# G009B.net
KiCad netlist of a schematic drawn in EAGLE
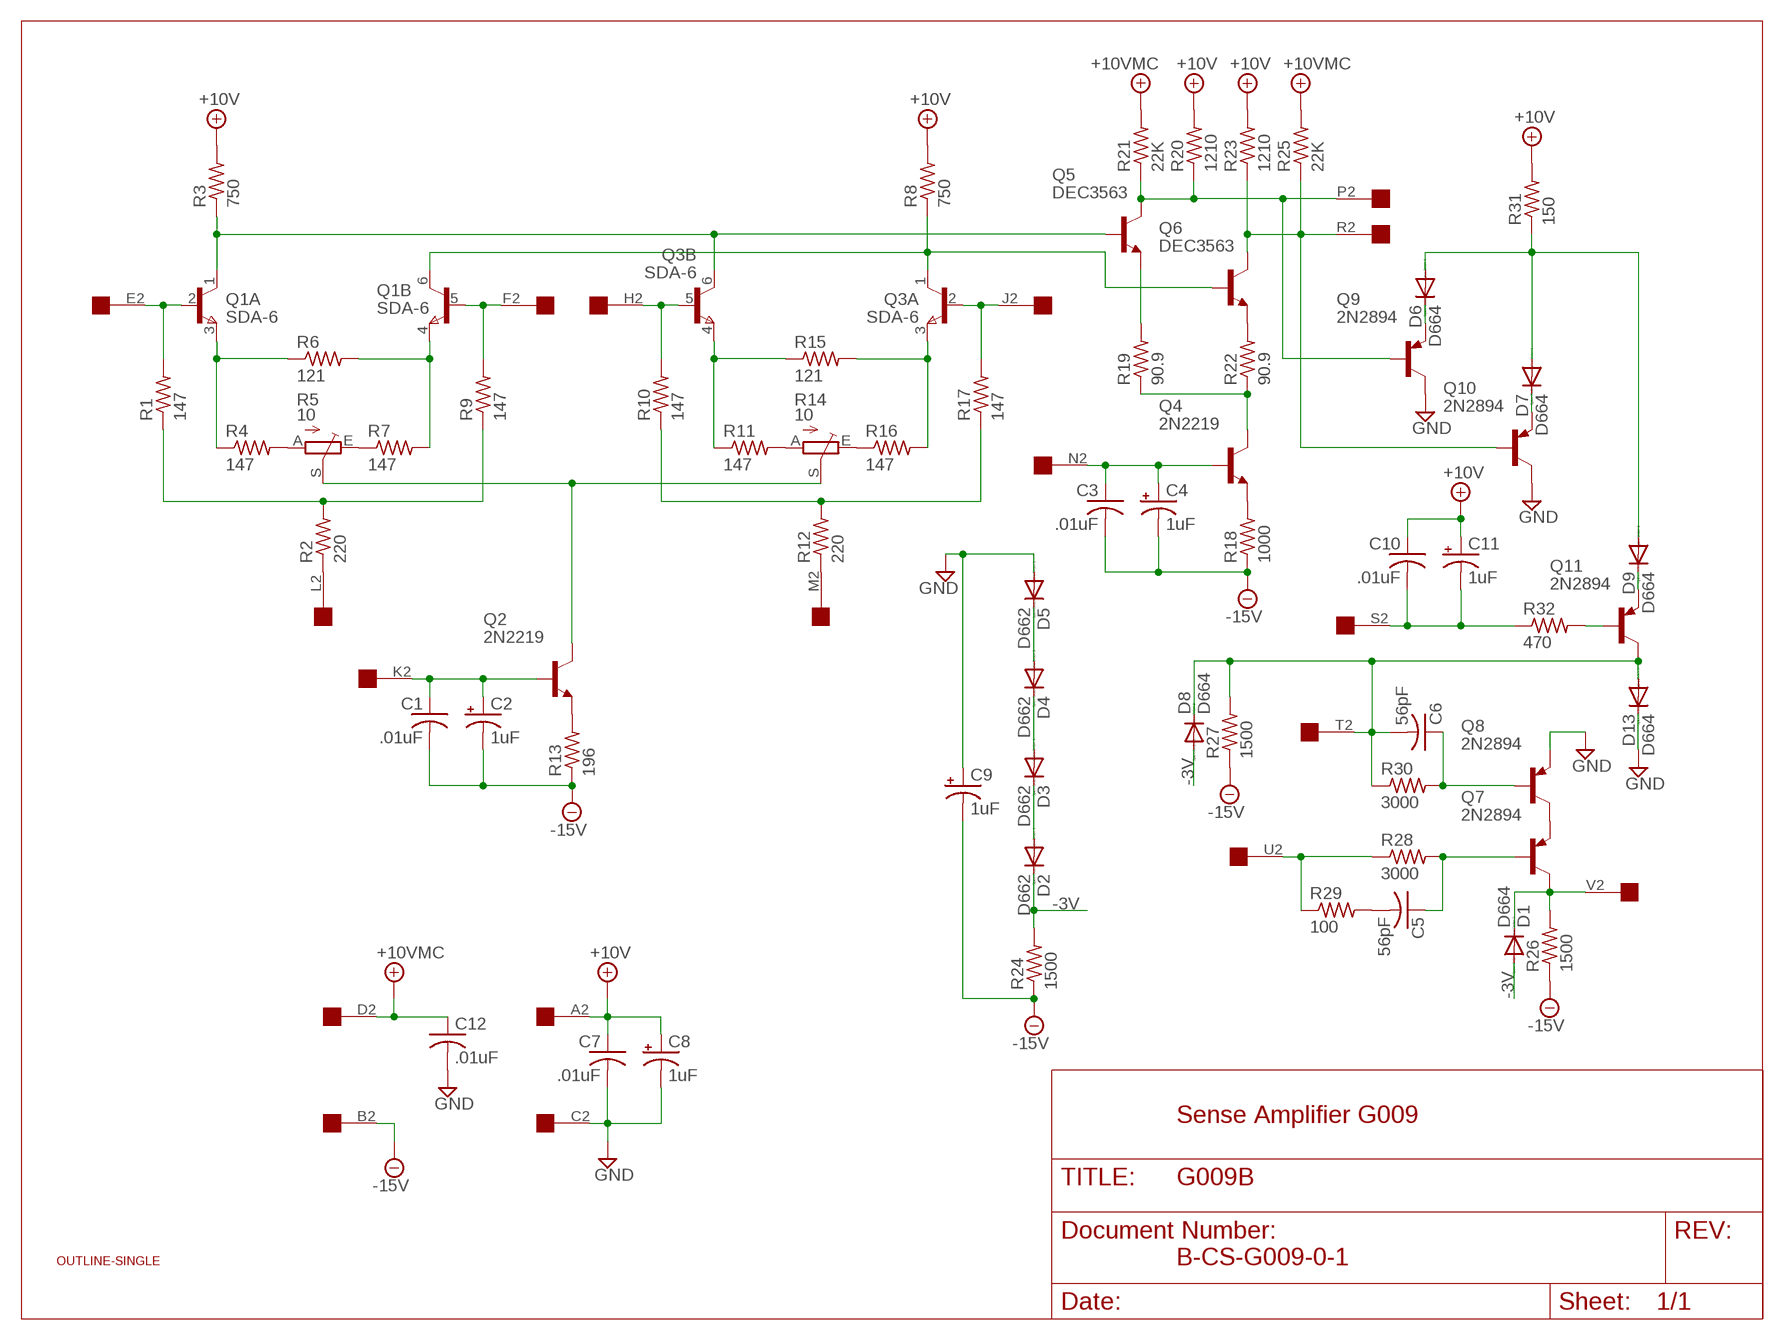
[diagram p0: schematic, sheet 1]

(export (version "E")
  (design (tool "Eeschema 10.0.6"))
  (components
    (comp (ref "C1")
      (value ".01uF")
      (footprint "eagle-import:C063-025X075")
      (libsource (lib "eagle-import") (part "C-US"))
    )
    (comp (ref "C2")
      (value "1uF")
      (footprint "eagle-import:E15-5")
      (libsource (lib "eagle-import") (part "CPOL-USE15-5AXIAL"))
    )
    (comp (ref "C3")
      (value ".01uF")
      (footprint "eagle-import:C063-025X075")
      (libsource (lib "eagle-import") (part "C-US"))
    )
    (comp (ref "C4")
      (value "1uF")
      (footprint "eagle-import:E15-5")
      (libsource (lib "eagle-import") (part "CPOL-USE15-5AXIAL"))
    )
    (comp (ref "C5")
      (value "56pF")
      (footprint "eagle-import:C150-054X183")
      (libsource (lib "eagle-import") (part "C-US150-054X183"))
    )
    (comp (ref "C6")
      (value "56pF")
      (footprint "eagle-import:C150-054X183")
      (libsource (lib "eagle-import") (part "C-US150-054X183"))
    )
    (comp (ref "C7")
      (value ".01uF")
      (footprint "eagle-import:C063-025X075")
      (libsource (lib "eagle-import") (part "C-US"))
    )
    (comp (ref "C8")
      (value "1uF")
      (footprint "eagle-import:E15-5")
      (libsource (lib "eagle-import") (part "CPOL-USE15-5AXIAL"))
    )
    (comp (ref "C9")
      (value "1uF")
      (footprint "eagle-import:E15-5")
      (libsource (lib "eagle-import") (part "CPOL-USE15-5AXIAL"))
    )
    (comp (ref "C10")
      (value ".01uF")
      (footprint "eagle-import:C063-025X075")
      (libsource (lib "eagle-import") (part "C-US"))
    )
    (comp (ref "C11")
      (value "1uF")
      (footprint "eagle-import:E15-5")
      (libsource (lib "eagle-import") (part "CPOL-USE15-5AXIAL"))
    )
    (comp (ref "C12")
      (value ".01uF")
      (footprint "eagle-import:C063-025X075")
      (libsource (lib "eagle-import") (part "C-US"))
    )
    (comp (ref "D1")
      (value "D664")
      (footprint "eagle-import:DO35-10")
      (libsource (lib "eagle-import") (part "DIODE-DO35-10"))
    )
    (comp (ref "D2")
      (value "D662")
      (footprint "eagle-import:DO35-10")
      (libsource (lib "eagle-import") (part "DIODE-DO35-10"))
    )
    (comp (ref "D3")
      (value "D662")
      (footprint "eagle-import:DO35-10")
      (libsource (lib "eagle-import") (part "DIODE-DO35-10"))
    )
    (comp (ref "D4")
      (value "D662")
      (footprint "eagle-import:DO35-10")
      (libsource (lib "eagle-import") (part "DIODE-DO35-10"))
    )
    (comp (ref "D5")
      (value "D662")
      (footprint "eagle-import:DO35-10")
      (libsource (lib "eagle-import") (part "DIODE-DO35-10"))
    )
    (comp (ref "D6")
      (value "D664")
      (footprint "eagle-import:DO35-10")
      (libsource (lib "eagle-import") (part "DIODE-DO35-10"))
    )
    (comp (ref "D7")
      (value "D664")
      (footprint "eagle-import:DO35-10")
      (libsource (lib "eagle-import") (part "DIODE-DO35-10"))
    )
    (comp (ref "D8")
      (value "D664")
      (footprint "eagle-import:DO35-10")
      (libsource (lib "eagle-import") (part "DIODE-DO35-10"))
    )
    (comp (ref "D9")
      (value "D664")
      (footprint "eagle-import:DO35-10")
      (libsource (lib "eagle-import") (part "DIODE-DO35-10"))
    )
    (comp (ref "D13")
      (value "D664")
      (footprint "eagle-import:DO35-10")
      (libsource (lib "eagle-import") (part "DIODE-DO35-10"))
    )
    (comp (ref "Q1")
      (value "SDA-6")
      (footprint "eagle-import:TO78")
      (libsource (lib "eagle-import") (part "MAT-01H"))
    )
    (comp (ref "Q2")
      (value "2N2219")
      (footprint "eagle-import:TO5")
      (libsource (lib "eagle-import") (part "2N2219"))
    )
    (comp (ref "Q3")
      (value "SDA-6")
      (footprint "eagle-import:TO78")
      (libsource (lib "eagle-import") (part "MAT-01H"))
    )
    (comp (ref "Q4")
      (value "2N2219")
      (footprint "eagle-import:TO5")
      (libsource (lib "eagle-import") (part "2N2219"))
    )
    (comp (ref "Q5")
      (value "DEC3563")
      (footprint "eagle-import:TO5")
      (libsource (lib "eagle-import") (part "-NPN-TO5"))
    )
    (comp (ref "Q6")
      (value "DEC3563")
      (footprint "eagle-import:TO5")
      (libsource (lib "eagle-import") (part "-NPN-TO5"))
    )
    (comp (ref "Q7")
      (value "2N2894")
      (footprint "eagle-import:TO5")
      (libsource (lib "eagle-import") (part "-PNP-TO5"))
    )
    (comp (ref "Q8")
      (value "2N2894")
      (footprint "eagle-import:TO5")
      (libsource (lib "eagle-import") (part "-PNP-TO5"))
    )
    (comp (ref "Q9")
      (value "2N2894")
      (footprint "eagle-import:TO5")
      (libsource (lib "eagle-import") (part "-PNP-TO5"))
    )
    (comp (ref "Q10")
      (value "2N2894")
      (footprint "eagle-import:TO5")
      (libsource (lib "eagle-import") (part "-PNP-TO5"))
    )
    (comp (ref "Q11")
      (value "2N2894")
      (footprint "eagle-import:TO5")
      (libsource (lib "eagle-import") (part "-PNP-TO5"))
    )
    (comp (ref "R1")
      (value "147")
      (footprint "eagle-import:0207_15")
      (libsource (lib "eagle-import") (part "R-US_0207/15"))
    )
    (comp (ref "R2")
      (value "220")
      (footprint "eagle-import:0207_10")
      (libsource (lib "eagle-import") (part "R-US_0207/10"))
    )
    (comp (ref "R3")
      (value "750")
      (footprint "eagle-import:0207_15")
      (libsource (lib "eagle-import") (part "R-US_0207/15"))
    )
    (comp (ref "R4")
      (value "147")
      (footprint "eagle-import:0207_15")
      (libsource (lib "eagle-import") (part "R-US_0207/15"))
    )
    (comp (ref "R5")
      (value "10")
      (footprint "eagle-import:CT6")
      (libsource (lib "eagle-import") (part "TRIM_EU-CT6"))
    )
    (comp (ref "R6")
      (value "121")
      (footprint "eagle-import:0207_15")
      (libsource (lib "eagle-import") (part "R-US_0207/15"))
    )
    (comp (ref "R7")
      (value "147")
      (footprint "eagle-import:0207_15")
      (libsource (lib "eagle-import") (part "R-US_0207/15"))
    )
    (comp (ref "R8")
      (value "750")
      (footprint "eagle-import:0207_15")
      (libsource (lib "eagle-import") (part "R-US_0207/15"))
    )
    (comp (ref "R9")
      (value "147")
      (footprint "eagle-import:0207_15")
      (libsource (lib "eagle-import") (part "R-US_0207/15"))
    )
    (comp (ref "R10")
      (value "147")
      (footprint "eagle-import:0207_15")
      (libsource (lib "eagle-import") (part "R-US_0207/15"))
    )
    (comp (ref "R11")
      (value "147")
      (footprint "eagle-import:0207_15")
      (libsource (lib "eagle-import") (part "R-US_0207/15"))
    )
    (comp (ref "R12")
      (value "220")
      (footprint "eagle-import:0207_10")
      (libsource (lib "eagle-import") (part "R-US_0207/10"))
    )
    (comp (ref "R13")
      (value "196")
      (footprint "eagle-import:0207_15")
      (libsource (lib "eagle-import") (part "R-US_0207/15"))
    )
    (comp (ref "R14")
      (value "10")
      (footprint "eagle-import:CT6")
      (libsource (lib "eagle-import") (part "TRIM_EU-CT6"))
    )
    (comp (ref "R15")
      (value "121")
      (footprint "eagle-import:0207_15")
      (libsource (lib "eagle-import") (part "R-US_0207/15"))
    )
    (comp (ref "R16")
      (value "147")
      (footprint "eagle-import:0207_15")
      (libsource (lib "eagle-import") (part "R-US_0207/15"))
    )
    (comp (ref "R17")
      (value "147")
      (footprint "eagle-import:0207_15")
      (libsource (lib "eagle-import") (part "R-US_0207/15"))
    )
    (comp (ref "R18")
      (value "1000")
      (footprint "eagle-import:0207_15")
      (libsource (lib "eagle-import") (part "R-US_0207/15"))
    )
    (comp (ref "R19")
      (value "90.9")
      (footprint "eagle-import:0207_15")
      (libsource (lib "eagle-import") (part "R-US_0207/15"))
    )
    (comp (ref "R20")
      (value "1210")
      (footprint "eagle-import:0207_15")
      (libsource (lib "eagle-import") (part "R-US_0207/15"))
    )
    (comp (ref "R21")
      (value "22K")
      (footprint "eagle-import:0207_10")
      (libsource (lib "eagle-import") (part "R-US_0207/10"))
    )
    (comp (ref "R22")
      (value "90.9")
      (footprint "eagle-import:0207_15")
      (libsource (lib "eagle-import") (part "R-US_0207/15"))
    )
    (comp (ref "R23")
      (value "1210")
      (footprint "eagle-import:0207_15")
      (libsource (lib "eagle-import") (part "R-US_0207/15"))
    )
    (comp (ref "R24")
      (value "1500")
      (footprint "eagle-import:0207_10")
      (libsource (lib "eagle-import") (part "R-US_0207/10"))
    )
    (comp (ref "R25")
      (value "22K")
      (footprint "eagle-import:0207_10")
      (libsource (lib "eagle-import") (part "R-US_0207/10"))
    )
    (comp (ref "R26")
      (value "1500")
      (footprint "eagle-import:0207_10")
      (libsource (lib "eagle-import") (part "R-US_0207/10"))
    )
    (comp (ref "R27")
      (value "1500")
      (footprint "eagle-import:0207_10")
      (libsource (lib "eagle-import") (part "R-US_0207/10"))
    )
    (comp (ref "R28")
      (value "3000")
      (footprint "eagle-import:0207_10")
      (libsource (lib "eagle-import") (part "R-US_0207/10"))
    )
    (comp (ref "R29")
      (value "100")
      (footprint "eagle-import:0207_10")
      (libsource (lib "eagle-import") (part "R-US_0207/10"))
    )
    (comp (ref "R30")
      (value "3000")
      (footprint "eagle-import:0207_10")
      (libsource (lib "eagle-import") (part "R-US_0207/10"))
    )
    (comp (ref "R31")
      (value "150")
      (footprint "eagle-import:0207_10")
      (libsource (lib "eagle-import") (part "R-US_0207/10"))
    )
    (comp (ref "R32")
      (value "470")
      (footprint "eagle-import:0207_10")
      (libsource (lib "eagle-import") (part "R-US_0207/10"))
    )
    (comp (ref "U$1")
      (value "OUTLINE-SINGLE")
      (footprint "eagle-import:SINGLE")
      (libsource (lib "eagle-import") (part "OUTLINE-SINGLE"))
    )
    (comp (ref "U$2")
      (value "EDGE-1")
      (footprint "eagle-import:EDGE-CON1")
      (libsource (lib "eagle-import") (part "EDGE-1"))
    )
  )
  (nets
    (net (code "1") (name "+10V") (class "Default")
      (node (ref "C10") (pin "1") (pinfunction "1_1") (pintype "passive"))
      (node (ref "C11") (pin "+") (pinfunction "+_+") (pintype "passive"))
      (node (ref "C7") (pin "1") (pinfunction "1_1") (pintype "passive"))
      (node (ref "C8") (pin "+") (pinfunction "+_+") (pintype "passive"))
      (node (ref "R20") (pin "2") (pinfunction "2_2") (pintype "passive"))
      (node (ref "R23") (pin "2") (pinfunction "2_2") (pintype "passive"))
      (node (ref "R3") (pin "2") (pinfunction "2_2") (pintype "passive"))
      (node (ref "R31") (pin "2") (pinfunction "2_2") (pintype "passive"))
      (node (ref "R8") (pin "2") (pinfunction "2_2") (pintype "passive"))
      (node (ref "U$2") (pin "A2") (pinfunction "1_A2") (pintype "bidirectional"))
    )
    (net (code "2") (name "+10VMC") (class "Default")
      (node (ref "C12") (pin "1") (pinfunction "1_1") (pintype "passive"))
      (node (ref "R21") (pin "2") (pinfunction "2_2") (pintype "passive"))
      (node (ref "R25") (pin "2") (pinfunction "2_2") (pintype "passive"))
      (node (ref "U$2") (pin "D2") (pinfunction "1_D2") (pintype "bidirectional"))
    )
    (net (code "3") (name "-15V") (class "Default")
      (node (ref "C1") (pin "2") (pinfunction "2_2") (pintype "passive"))
      (node (ref "C2") (pin "-") (pinfunction "-_-") (pintype "passive"))
      (node (ref "C3") (pin "2") (pinfunction "2_2") (pintype "passive"))
      (node (ref "C4") (pin "-") (pinfunction "-_-") (pintype "passive"))
      (node (ref "C9") (pin "-") (pinfunction "-_-") (pintype "passive"))
      (node (ref "R13") (pin "1") (pinfunction "1_1") (pintype "passive"))
      (node (ref "R18") (pin "1") (pinfunction "1_1") (pintype "passive"))
      (node (ref "R24") (pin "1") (pinfunction "1_1") (pintype "passive"))
      (node (ref "R26") (pin "1") (pinfunction "1_1") (pintype "passive"))
      (node (ref "R27") (pin "1") (pinfunction "1_1") (pintype "passive"))
      (node (ref "U$2") (pin "B2") (pinfunction "1_B2") (pintype "bidirectional"))
    )
    (net (code "4") (name "/-3V") (class "Default")
      (node (ref "D1") (pin "A") (pinfunction "A_A") (pintype "passive"))
      (node (ref "D2") (pin "C") (pinfunction "C_C") (pintype "passive"))
      (node (ref "D8") (pin "A") (pinfunction "A_A") (pintype "passive"))
      (node (ref "R24") (pin "2") (pinfunction "2_2") (pintype "passive"))
    )
    (net (code "5") (name "GND") (class "Default")
      (node (ref "C12") (pin "2") (pinfunction "2_2") (pintype "passive"))
      (node (ref "C7") (pin "2") (pinfunction "2_2") (pintype "passive"))
      (node (ref "C8") (pin "-") (pinfunction "-_-") (pintype "passive"))
      (node (ref "C9") (pin "+") (pinfunction "+_+") (pintype "passive"))
      (node (ref "D13") (pin "C") (pinfunction "C_C") (pintype "passive"))
      (node (ref "D5") (pin "A") (pinfunction "A_A") (pintype "passive"))
      (node (ref "Q10") (pin "3") (pinfunction "C_3") (pintype "passive"))
      (node (ref "Q8") (pin "1") (pinfunction "E_1") (pintype "passive"))
      (node (ref "Q9") (pin "3") (pinfunction "C_3") (pintype "passive"))
      (node (ref "U$2") (pin "C2") (pinfunction "1_C2") (pintype "bidirectional"))
    )
    (net (code "6") (name "Net-(C5-Pad2)") (class "Default")
      (node (ref "C5") (pin "2") (pinfunction "2_2") (pintype "passive"))
      (node (ref "R29") (pin "2") (pinfunction "2_2") (pintype "passive"))
    )
    (net (code "7") (name "Net-(D2-PadA)") (class "Default")
      (node (ref "D2") (pin "A") (pinfunction "A_A") (pintype "passive"))
      (node (ref "D3") (pin "C") (pinfunction "C_C") (pintype "passive"))
    )
    (net (code "8") (name "Net-(D3-PadA)") (class "Default")
      (node (ref "D3") (pin "A") (pinfunction "A_A") (pintype "passive"))
      (node (ref "D4") (pin "C") (pinfunction "C_C") (pintype "passive"))
    )
    (net (code "9") (name "Net-(D4-PadA)") (class "Default")
      (node (ref "D4") (pin "A") (pinfunction "A_A") (pintype "passive"))
      (node (ref "D5") (pin "C") (pinfunction "C_C") (pintype "passive"))
    )
    (net (code "10") (name "Net-(D6-PadA)") (class "Default")
      (node (ref "D6") (pin "A") (pinfunction "A_A") (pintype "passive"))
      (node (ref "D7") (pin "A") (pinfunction "A_A") (pintype "passive"))
      (node (ref "D9") (pin "A") (pinfunction "A_A") (pintype "passive"))
      (node (ref "R31") (pin "1") (pinfunction "1_1") (pintype "passive"))
    )
    (net (code "11") (name "Net-(Q1A-B)") (class "Default")
      (node (ref "Q1") (pin "2") (pinfunction "B_2") (pintype "passive"))
      (node (ref "R1") (pin "2") (pinfunction "2_2") (pintype "passive"))
      (node (ref "U$2") (pin "E2") (pinfunction "1_E2") (pintype "bidirectional"))
    )
    (net (code "12") (name "Net-(Q1A-C)") (class "Default")
      (node (ref "Q1") (pin "1") (pinfunction "C_1") (pintype "passive"))
      (node (ref "Q3") (pin "6") (pinfunction "C_6") (pintype "passive"))
      (node (ref "Q5") (pin "2") (pinfunction "B_2") (pintype "passive"))
      (node (ref "R3") (pin "1") (pinfunction "1_1") (pintype "passive"))
    )
    (net (code "13") (name "Net-(Q1A-E)") (class "Default")
      (node (ref "Q1") (pin "3") (pinfunction "E_3") (pintype "passive"))
      (node (ref "R4") (pin "1") (pinfunction "1_1") (pintype "passive"))
      (node (ref "R6") (pin "1") (pinfunction "1_1") (pintype "passive"))
    )
    (net (code "14") (name "Net-(Q1B-B)") (class "Default")
      (node (ref "Q1") (pin "5") (pinfunction "B_5") (pintype "passive"))
      (node (ref "R9") (pin "2") (pinfunction "2_2") (pintype "passive"))
      (node (ref "U$2") (pin "F2") (pinfunction "1_F2") (pintype "bidirectional"))
    )
    (net (code "15") (name "Net-(Q1B-C)") (class "Default")
      (node (ref "Q1") (pin "6") (pinfunction "C_6") (pintype "passive"))
      (node (ref "Q3") (pin "1") (pinfunction "C_1") (pintype "passive"))
      (node (ref "Q6") (pin "2") (pinfunction "B_2") (pintype "passive"))
      (node (ref "R8") (pin "1") (pinfunction "1_1") (pintype "passive"))
    )
    (net (code "16") (name "Net-(Q1B-E)") (class "Default")
      (node (ref "Q1") (pin "4") (pinfunction "E_4") (pintype "passive"))
      (node (ref "R6") (pin "2") (pinfunction "2_2") (pintype "passive"))
      (node (ref "R7") (pin "2") (pinfunction "2_2") (pintype "passive"))
    )
    (net (code "17") (name "Net-(Q2-B)") (class "Default")
      (node (ref "C1") (pin "1") (pinfunction "1_1") (pintype "passive"))
      (node (ref "C2") (pin "+") (pinfunction "+_+") (pintype "passive"))
      (node (ref "Q2") (pin "2") (pinfunction "B_2") (pintype "passive"))
      (node (ref "U$2") (pin "K2") (pinfunction "1_K2") (pintype "bidirectional"))
    )
    (net (code "18") (name "Net-(Q2-C)") (class "Default")
      (node (ref "Q2") (pin "3") (pinfunction "C_3") (pintype "passive"))
      (node (ref "R14") (pin "S") (pinfunction "S_S") (pintype "passive"))
      (node (ref "R5") (pin "S") (pinfunction "S_S") (pintype "passive"))
    )
    (net (code "19") (name "Net-(Q2-E)") (class "Default")
      (node (ref "Q2") (pin "1") (pinfunction "E_1") (pintype "passive"))
      (node (ref "R13") (pin "2") (pinfunction "2_2") (pintype "passive"))
    )
    (net (code "20") (name "Net-(Q3A-B)") (class "Default")
      (node (ref "Q3") (pin "2") (pinfunction "B_2") (pintype "passive"))
      (node (ref "R17") (pin "2") (pinfunction "2_2") (pintype "passive"))
      (node (ref "U$2") (pin "J2") (pinfunction "1_J2") (pintype "bidirectional"))
    )
    (net (code "21") (name "Net-(Q3A-E)") (class "Default")
      (node (ref "Q3") (pin "3") (pinfunction "E_3") (pintype "passive"))
      (node (ref "R15") (pin "2") (pinfunction "2_2") (pintype "passive"))
      (node (ref "R16") (pin "2") (pinfunction "2_2") (pintype "passive"))
    )
    (net (code "22") (name "Net-(Q3B-B)") (class "Default")
      (node (ref "Q3") (pin "5") (pinfunction "B_5") (pintype "passive"))
      (node (ref "R10") (pin "2") (pinfunction "2_2") (pintype "passive"))
      (node (ref "U$2") (pin "H2") (pinfunction "1_H2") (pintype "bidirectional"))
    )
    (net (code "23") (name "Net-(Q3B-E)") (class "Default")
      (node (ref "Q3") (pin "4") (pinfunction "E_4") (pintype "passive"))
      (node (ref "R11") (pin "1") (pinfunction "1_1") (pintype "passive"))
      (node (ref "R15") (pin "1") (pinfunction "1_1") (pintype "passive"))
    )
    (net (code "24") (name "Net-(Q4-B)") (class "Default")
      (node (ref "C3") (pin "1") (pinfunction "1_1") (pintype "passive"))
      (node (ref "C4") (pin "+") (pinfunction "+_+") (pintype "passive"))
      (node (ref "Q4") (pin "2") (pinfunction "B_2") (pintype "passive"))
      (node (ref "U$2") (pin "N2") (pinfunction "1_N2") (pintype "bidirectional"))
    )
    (net (code "25") (name "Net-(Q4-C)") (class "Default")
      (node (ref "Q4") (pin "3") (pinfunction "C_3") (pintype "passive"))
      (node (ref "R19") (pin "1") (pinfunction "1_1") (pintype "passive"))
      (node (ref "R22") (pin "1") (pinfunction "1_1") (pintype "passive"))
    )
    (net (code "26") (name "Net-(Q4-E)") (class "Default")
      (node (ref "Q4") (pin "1") (pinfunction "E_1") (pintype "passive"))
      (node (ref "R18") (pin "2") (pinfunction "2_2") (pintype "passive"))
    )
    (net (code "27") (name "Net-(Q5-C)") (class "Default")
      (node (ref "Q5") (pin "3") (pinfunction "C_3") (pintype "passive"))
      (node (ref "Q9") (pin "2") (pinfunction "B_2") (pintype "passive"))
      (node (ref "R20") (pin "1") (pinfunction "1_1") (pintype "passive"))
      (node (ref "R21") (pin "1") (pinfunction "1_1") (pintype "passive"))
      (node (ref "U$2") (pin "P2") (pinfunction "1_P2") (pintype "bidirectional"))
    )
    (net (code "28") (name "Net-(Q5-E)") (class "Default")
      (node (ref "Q5") (pin "1") (pinfunction "E_1") (pintype "passive"))
      (node (ref "R19") (pin "2") (pinfunction "2_2") (pintype "passive"))
    )
    (net (code "29") (name "Net-(Q6-E)") (class "Default")
      (node (ref "Q6") (pin "1") (pinfunction "E_1") (pintype "passive"))
      (node (ref "R22") (pin "2") (pinfunction "2_2") (pintype "passive"))
    )
    (net (code "30") (name "Net-(Q7-B)") (class "Default")
      (node (ref "C5") (pin "1") (pinfunction "1_1") (pintype "passive"))
      (node (ref "Q7") (pin "2") (pinfunction "B_2") (pintype "passive"))
      (node (ref "R28") (pin "2") (pinfunction "2_2") (pintype "passive"))
    )
    (net (code "31") (name "Net-(Q7-C)") (class "Default")
      (node (ref "D1") (pin "C") (pinfunction "C_C") (pintype "passive"))
      (node (ref "Q7") (pin "3") (pinfunction "C_3") (pintype "passive"))
      (node (ref "R26") (pin "2") (pinfunction "2_2") (pintype "passive"))
      (node (ref "U$2") (pin "V2") (pinfunction "1_V2") (pintype "bidirectional"))
    )
    (net (code "32") (name "Net-(Q7-E)") (class "Default")
      (node (ref "Q7") (pin "1") (pinfunction "E_1") (pintype "passive"))
      (node (ref "Q8") (pin "3") (pinfunction "C_3") (pintype "passive"))
    )
    (net (code "33") (name "Net-(Q8-B)") (class "Default")
      (node (ref "C6") (pin "1") (pinfunction "1_1") (pintype "passive"))
      (node (ref "Q8") (pin "2") (pinfunction "B_2") (pintype "passive"))
      (node (ref "R30") (pin "2") (pinfunction "2_2") (pintype "passive"))
    )
    (net (code "34") (name "Net-(Q9-E)") (class "Default")
      (node (ref "D6") (pin "C") (pinfunction "C_C") (pintype "passive"))
      (node (ref "Q9") (pin "1") (pinfunction "E_1") (pintype "passive"))
    )
    (net (code "35") (name "Net-(Q10-B)") (class "Default")
      (node (ref "Q10") (pin "2") (pinfunction "B_2") (pintype "passive"))
      (node (ref "Q6") (pin "3") (pinfunction "C_3") (pintype "passive"))
      (node (ref "R23") (pin "1") (pinfunction "1_1") (pintype "passive"))
      (node (ref "R25") (pin "1") (pinfunction "1_1") (pintype "passive"))
      (node (ref "U$2") (pin "R2") (pinfunction "1_R2") (pintype "bidirectional"))
    )
    (net (code "36") (name "Net-(Q10-E)") (class "Default")
      (node (ref "D7") (pin "C") (pinfunction "C_C") (pintype "passive"))
      (node (ref "Q10") (pin "1") (pinfunction "E_1") (pintype "passive"))
    )
    (net (code "37") (name "Net-(Q11-B)") (class "Default")
      (node (ref "Q11") (pin "2") (pinfunction "B_2") (pintype "passive"))
      (node (ref "R32") (pin "2") (pinfunction "2_2") (pintype "passive"))
    )
    (net (code "38") (name "Net-(Q11-C)") (class "Default")
      (node (ref "C6") (pin "2") (pinfunction "2_2") (pintype "passive"))
      (node (ref "D13") (pin "A") (pinfunction "A_A") (pintype "passive"))
      (node (ref "D8") (pin "C") (pinfunction "C_C") (pintype "passive"))
      (node (ref "Q11") (pin "3") (pinfunction "C_3") (pintype "passive"))
      (node (ref "R27") (pin "2") (pinfunction "2_2") (pintype "passive"))
      (node (ref "R30") (pin "1") (pinfunction "1_1") (pintype "passive"))
      (node (ref "U$2") (pin "T2") (pinfunction "1_T2") (pintype "bidirectional"))
    )
    (net (code "39") (name "Net-(Q11-E)") (class "Default")
      (node (ref "D9") (pin "C") (pinfunction "C_C") (pintype "passive"))
      (node (ref "Q11") (pin "1") (pinfunction "E_1") (pintype "passive"))
    )
    (net (code "40") (name "Net-(R1-Pad1)") (class "Default")
      (node (ref "R1") (pin "1") (pinfunction "1_1") (pintype "passive"))
      (node (ref "R2") (pin "2") (pinfunction "2_2") (pintype "passive"))
      (node (ref "R9") (pin "1") (pinfunction "1_1") (pintype "passive"))
    )
    (net (code "41") (name "Net-(R4-Pad2)") (class "Default")
      (node (ref "R4") (pin "2") (pinfunction "2_2") (pintype "passive"))
      (node (ref "R5") (pin "A") (pinfunction "A_A") (pintype "passive"))
    )
    (net (code "42") (name "Net-(R5-PadE)") (class "Default")
      (node (ref "R5") (pin "E") (pinfunction "E_E") (pintype "passive"))
      (node (ref "R7") (pin "1") (pinfunction "1_1") (pintype "passive"))
    )
    (net (code "43") (name "Net-(R10-Pad1)") (class "Default")
      (node (ref "R10") (pin "1") (pinfunction "1_1") (pintype "passive"))
      (node (ref "R12") (pin "2") (pinfunction "2_2") (pintype "passive"))
      (node (ref "R17") (pin "1") (pinfunction "1_1") (pintype "passive"))
    )
    (net (code "44") (name "Net-(R11-Pad2)") (class "Default")
      (node (ref "R11") (pin "2") (pinfunction "2_2") (pintype "passive"))
      (node (ref "R14") (pin "A") (pinfunction "A_A") (pintype "passive"))
    )
    (net (code "45") (name "Net-(R14-PadE)") (class "Default")
      (node (ref "R14") (pin "E") (pinfunction "E_E") (pintype "passive"))
      (node (ref "R16") (pin "1") (pinfunction "1_1") (pintype "passive"))
    )
    (net (code "46") (name "Net-(U$2J-1)") (class "Default")
      (node (ref "R2") (pin "1") (pinfunction "1_1") (pintype "passive"))
      (node (ref "U$2") (pin "L2") (pinfunction "1_L2") (pintype "bidirectional"))
    )
    (net (code "47") (name "Net-(U$2K-1)") (class "Default")
      (node (ref "R12") (pin "1") (pinfunction "1_1") (pintype "passive"))
      (node (ref "U$2") (pin "M2") (pinfunction "1_M2") (pintype "bidirectional"))
    )
    (net (code "48") (name "Net-(U$2O-1)") (class "Default")
      (node (ref "C10") (pin "2") (pinfunction "2_2") (pintype "passive"))
      (node (ref "C11") (pin "-") (pinfunction "-_-") (pintype "passive"))
      (node (ref "R32") (pin "1") (pinfunction "1_1") (pintype "passive"))
      (node (ref "U$2") (pin "S2") (pinfunction "1_S2") (pintype "bidirectional"))
    )
    (net (code "49") (name "Net-(U$2Q-1)") (class "Default")
      (node (ref "R28") (pin "1") (pinfunction "1_1") (pintype "passive"))
      (node (ref "R29") (pin "1") (pinfunction "1_1") (pintype "passive"))
      (node (ref "U$2") (pin "U2") (pinfunction "1_U2") (pintype "bidirectional"))
    )
  )
)
